# arcade2.net
KiCad netlist of a schematic drawn in EAGLE
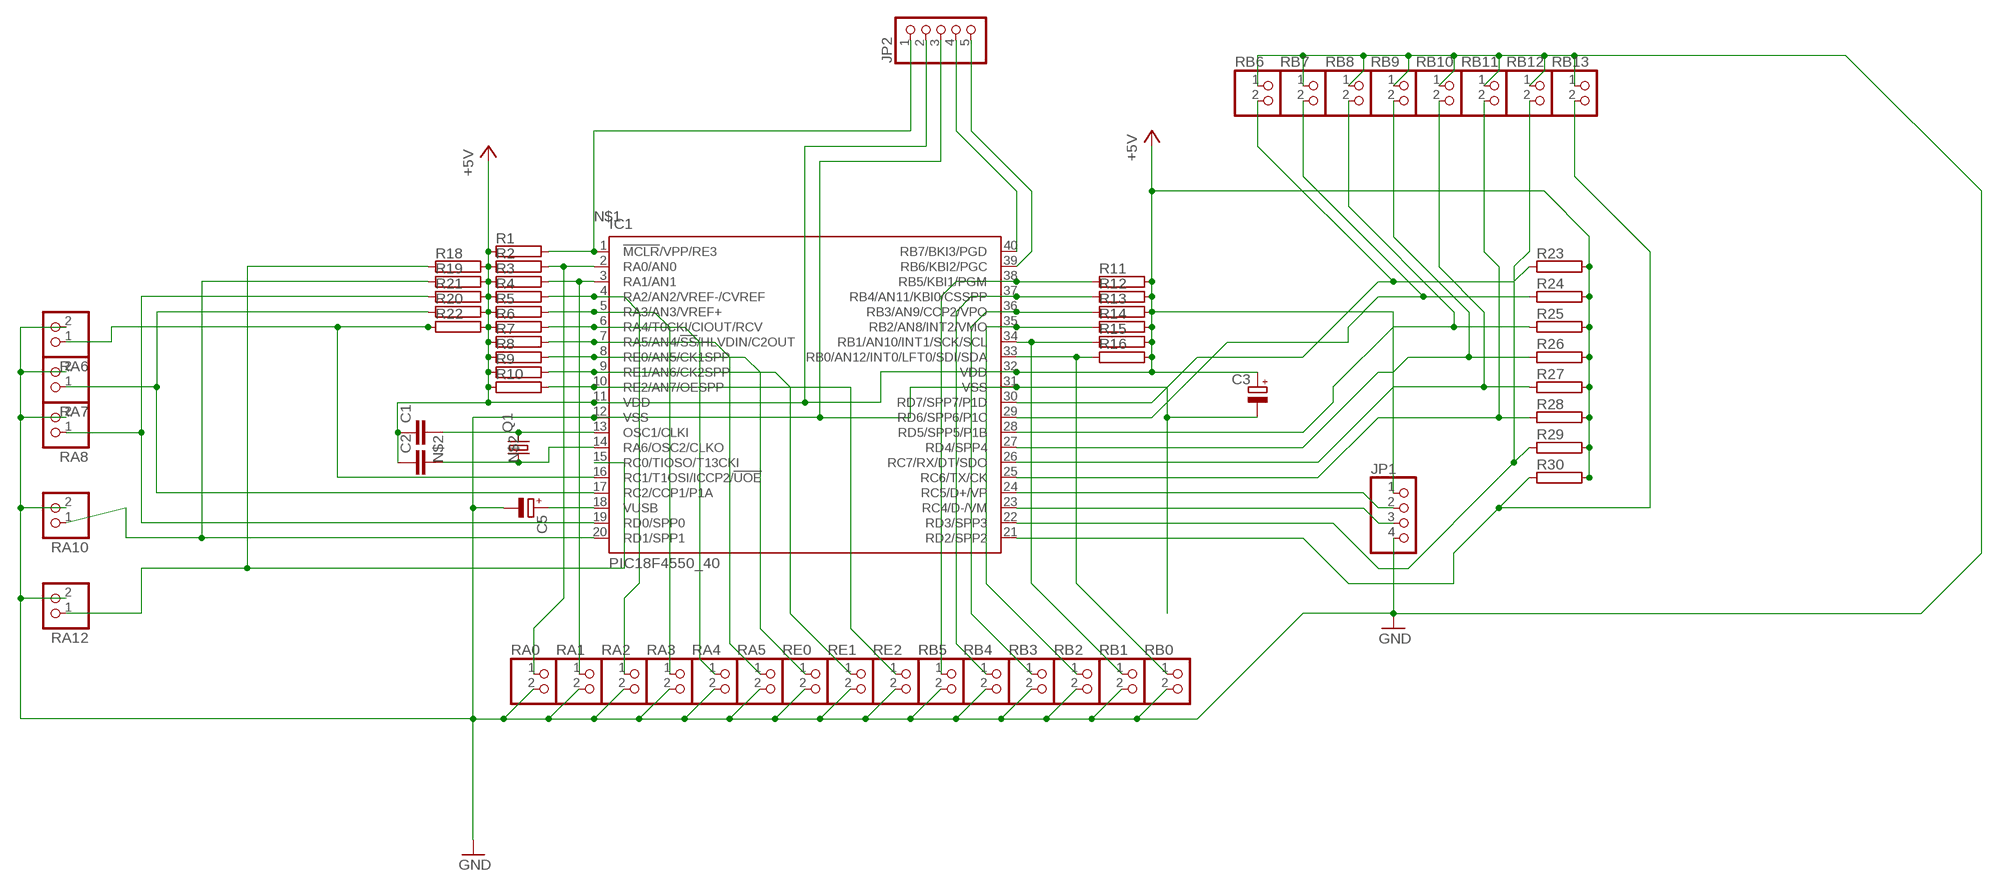
[diagram p0: schematic, sheet 1]

(export (version "E")
  (design (tool "Eeschema 10.0.6"))
  (components
    (comp (ref "C1")
      (value "C10/4")
      (footprint "eagle-import:C10B4")
      (libsource (lib "eagle-import") (part "C10/4"))
    )
    (comp (ref "C2")
      (value "C10/4")
      (footprint "eagle-import:C10B4")
      (libsource (lib "eagle-import") (part "C10/4"))
    )
    (comp (ref "C3")
      (value "CPOL-EUB45181C")
      (footprint "eagle-import:B45181C")
      (libsource (lib "eagle-import") (part "CPOL-EUB45181C"))
    )
    (comp (ref "C5")
      (value "CPOL-EUB45181C")
      (footprint "eagle-import:B45181C")
      (libsource (lib "eagle-import") (part "CPOL-EUB45181C"))
    )
    (comp (ref "IC1")
      (value "PIC18F4550_40")
      (footprint "eagle-import:DIL40")
      (fields (field (name "MF") "MICROCHIP") (field (name "MPN") "PIC18F4550-I/P"))
      (libsource (lib "eagle-import") (part "PIC18F4_40550"))
    )
    (comp (ref "JP1")
      (value "PINHD-1X4/90")
      (footprint "eagle-import:1X04_90")
      (libsource (lib "eagle-import") (part "PINHD-1X4/90"))
    )
    (comp (ref "JP2")
      (value "PINHD-1X5/90")
      (footprint "eagle-import:1X05_90")
      (libsource (lib "eagle-import") (part "PINHD-1X5/90"))
    )
    (comp (ref "Q1")
      (value "CRYSTALHC33U-V")
      (footprint "eagle-import:HC33U-V")
      (libsource (lib "eagle-import") (part "CRYSTALHC33U-V"))
    )
    (comp (ref "R1")
      (value "RAC01")
      (footprint "eagle-import:AC01")
      (libsource (lib "eagle-import") (part "RAC01"))
    )
    (comp (ref "R2")
      (value "RAC01")
      (footprint "eagle-import:AC01")
      (libsource (lib "eagle-import") (part "RAC01"))
    )
    (comp (ref "R3")
      (value "RAC01")
      (footprint "eagle-import:AC01")
      (libsource (lib "eagle-import") (part "RAC01"))
    )
    (comp (ref "R4")
      (value "RAC01")
      (footprint "eagle-import:AC01")
      (libsource (lib "eagle-import") (part "RAC01"))
    )
    (comp (ref "R5")
      (value "RAC01")
      (footprint "eagle-import:AC01")
      (libsource (lib "eagle-import") (part "RAC01"))
    )
    (comp (ref "R6")
      (value "RAC01")
      (footprint "eagle-import:AC01")
      (libsource (lib "eagle-import") (part "RAC01"))
    )
    (comp (ref "R7")
      (value "RAC01")
      (footprint "eagle-import:AC01")
      (libsource (lib "eagle-import") (part "RAC01"))
    )
    (comp (ref "R8")
      (value "RAC01")
      (footprint "eagle-import:AC01")
      (libsource (lib "eagle-import") (part "RAC01"))
    )
    (comp (ref "R9")
      (value "RAC01")
      (footprint "eagle-import:AC01")
      (libsource (lib "eagle-import") (part "RAC01"))
    )
    (comp (ref "R10")
      (value "RAC01")
      (footprint "eagle-import:AC01")
      (libsource (lib "eagle-import") (part "RAC01"))
    )
    (comp (ref "R11")
      (value "RAC01")
      (footprint "eagle-import:AC01")
      (libsource (lib "eagle-import") (part "RAC01"))
    )
    (comp (ref "R12")
      (value "RAC01")
      (footprint "eagle-import:AC01")
      (libsource (lib "eagle-import") (part "RAC01"))
    )
    (comp (ref "R13")
      (value "RAC01")
      (footprint "eagle-import:AC01")
      (libsource (lib "eagle-import") (part "RAC01"))
    )
    (comp (ref "R14")
      (value "RAC01")
      (footprint "eagle-import:AC01")
      (libsource (lib "eagle-import") (part "RAC01"))
    )
    (comp (ref "R15")
      (value "RAC01")
      (footprint "eagle-import:AC01")
      (libsource (lib "eagle-import") (part "RAC01"))
    )
    (comp (ref "R16")
      (value "RAC01")
      (footprint "eagle-import:AC01")
      (libsource (lib "eagle-import") (part "RAC01"))
    )
    (comp (ref "R18")
      (value "RAC01")
      (footprint "eagle-import:AC01")
      (libsource (lib "eagle-import") (part "RAC01"))
    )
    (comp (ref "R19")
      (value "RAC01")
      (footprint "eagle-import:AC01")
      (libsource (lib "eagle-import") (part "RAC01"))
    )
    (comp (ref "R20")
      (value "RAC01")
      (footprint "eagle-import:AC01")
      (libsource (lib "eagle-import") (part "RAC01"))
    )
    (comp (ref "R21")
      (value "RAC01")
      (footprint "eagle-import:AC01")
      (libsource (lib "eagle-import") (part "RAC01"))
    )
    (comp (ref "R22")
      (value "RAC01")
      (footprint "eagle-import:AC01")
      (libsource (lib "eagle-import") (part "RAC01"))
    )
    (comp (ref "R23")
      (value "RAC01")
      (footprint "eagle-import:AC01")
      (libsource (lib "eagle-import") (part "RAC01"))
    )
    (comp (ref "R24")
      (value "RAC01")
      (footprint "eagle-import:AC01")
      (libsource (lib "eagle-import") (part "RAC01"))
    )
    (comp (ref "R25")
      (value "RAC01")
      (footprint "eagle-import:AC01")
      (libsource (lib "eagle-import") (part "RAC01"))
    )
    (comp (ref "R26")
      (value "RAC01")
      (footprint "eagle-import:AC01")
      (libsource (lib "eagle-import") (part "RAC01"))
    )
    (comp (ref "R27")
      (value "RAC01")
      (footprint "eagle-import:AC01")
      (libsource (lib "eagle-import") (part "RAC01"))
    )
    (comp (ref "R28")
      (value "RAC01")
      (footprint "eagle-import:AC01")
      (libsource (lib "eagle-import") (part "RAC01"))
    )
    (comp (ref "R29")
      (value "RAC01")
      (footprint "eagle-import:AC01")
      (libsource (lib "eagle-import") (part "RAC01"))
    )
    (comp (ref "R30")
      (value "RAC01")
      (footprint "eagle-import:AC01")
      (libsource (lib "eagle-import") (part "RAC01"))
    )
    (comp (ref "RA0")
      (value "PINHD-1X2/90")
      (footprint "eagle-import:1X02_90")
      (libsource (lib "eagle-import") (part "PINHD-1X2/90"))
    )
    (comp (ref "RA1")
      (value "PINHD-1X2/90")
      (footprint "eagle-import:1X02_90")
      (libsource (lib "eagle-import") (part "PINHD-1X2/90"))
    )
    (comp (ref "RA2")
      (value "PINHD-1X2/90")
      (footprint "eagle-import:1X02_90")
      (libsource (lib "eagle-import") (part "PINHD-1X2/90"))
    )
    (comp (ref "RA3")
      (value "PINHD-1X2/90")
      (footprint "eagle-import:1X02_90")
      (libsource (lib "eagle-import") (part "PINHD-1X2/90"))
    )
    (comp (ref "RA4")
      (value "PINHD-1X2/90")
      (footprint "eagle-import:1X02_90")
      (libsource (lib "eagle-import") (part "PINHD-1X2/90"))
    )
    (comp (ref "RA5")
      (value "PINHD-1X2/90")
      (footprint "eagle-import:1X02_90")
      (libsource (lib "eagle-import") (part "PINHD-1X2/90"))
    )
    (comp (ref "RA6")
      (value "PINHD-1X2/90")
      (footprint "eagle-import:1X02_90")
      (libsource (lib "eagle-import") (part "PINHD-1X2/90"))
    )
    (comp (ref "RA7")
      (value "PINHD-1X2/90")
      (footprint "eagle-import:1X02_90")
      (libsource (lib "eagle-import") (part "PINHD-1X2/90"))
    )
    (comp (ref "RA8")
      (value "PINHD-1X2/90")
      (footprint "eagle-import:1X02_90")
      (libsource (lib "eagle-import") (part "PINHD-1X2/90"))
    )
    (comp (ref "RA10")
      (value "PINHD-1X2/90")
      (footprint "eagle-import:1X02_90")
      (libsource (lib "eagle-import") (part "PINHD-1X2/90"))
    )
    (comp (ref "RA12")
      (value "PINHD-1X2/90")
      (footprint "eagle-import:1X02_90")
      (libsource (lib "eagle-import") (part "PINHD-1X2/90"))
    )
    (comp (ref "RB0")
      (value "PINHD-1X2/90")
      (footprint "eagle-import:1X02_90")
      (libsource (lib "eagle-import") (part "PINHD-1X2/90"))
    )
    (comp (ref "RB1")
      (value "PINHD-1X2/90")
      (footprint "eagle-import:1X02_90")
      (libsource (lib "eagle-import") (part "PINHD-1X2/90"))
    )
    (comp (ref "RB2")
      (value "PINHD-1X2/90")
      (footprint "eagle-import:1X02_90")
      (libsource (lib "eagle-import") (part "PINHD-1X2/90"))
    )
    (comp (ref "RB3")
      (value "PINHD-1X2/90")
      (footprint "eagle-import:1X02_90")
      (libsource (lib "eagle-import") (part "PINHD-1X2/90"))
    )
    (comp (ref "RB4")
      (value "PINHD-1X2/90")
      (footprint "eagle-import:1X02_90")
      (libsource (lib "eagle-import") (part "PINHD-1X2/90"))
    )
    (comp (ref "RB5")
      (value "PINHD-1X2/90")
      (footprint "eagle-import:1X02_90")
      (libsource (lib "eagle-import") (part "PINHD-1X2/90"))
    )
    (comp (ref "RB6")
      (value "PINHD-1X2/90")
      (footprint "eagle-import:1X02_90")
      (libsource (lib "eagle-import") (part "PINHD-1X2/90"))
    )
    (comp (ref "RB7")
      (value "PINHD-1X2/90")
      (footprint "eagle-import:1X02_90")
      (libsource (lib "eagle-import") (part "PINHD-1X2/90"))
    )
    (comp (ref "RB8")
      (value "PINHD-1X2/90")
      (footprint "eagle-import:1X02_90")
      (libsource (lib "eagle-import") (part "PINHD-1X2/90"))
    )
    (comp (ref "RB9")
      (value "PINHD-1X2/90")
      (footprint "eagle-import:1X02_90")
      (libsource (lib "eagle-import") (part "PINHD-1X2/90"))
    )
    (comp (ref "RB10")
      (value "PINHD-1X2/90")
      (footprint "eagle-import:1X02_90")
      (libsource (lib "eagle-import") (part "PINHD-1X2/90"))
    )
    (comp (ref "RB11")
      (value "PINHD-1X2/90")
      (footprint "eagle-import:1X02_90")
      (libsource (lib "eagle-import") (part "PINHD-1X2/90"))
    )
    (comp (ref "RB12")
      (value "PINHD-1X2/90")
      (footprint "eagle-import:1X02_90")
      (libsource (lib "eagle-import") (part "PINHD-1X2/90"))
    )
    (comp (ref "RB13")
      (value "PINHD-1X2/90")
      (footprint "eagle-import:1X02_90")
      (libsource (lib "eagle-import") (part "PINHD-1X2/90"))
    )
    (comp (ref "RE0")
      (value "PINHD-1X2/90")
      (footprint "eagle-import:1X02_90")
      (libsource (lib "eagle-import") (part "PINHD-1X2/90"))
    )
    (comp (ref "RE1")
      (value "PINHD-1X2/90")
      (footprint "eagle-import:1X02_90")
      (libsource (lib "eagle-import") (part "PINHD-1X2/90"))
    )
    (comp (ref "RE2")
      (value "PINHD-1X2/90")
      (footprint "eagle-import:1X02_90")
      (libsource (lib "eagle-import") (part "PINHD-1X2/90"))
    )
  )
  (nets
    (net (code "1") (name "+5V") (class "Default")
      (node (ref "C1") (pin "1") (pinfunction "1_1") (pintype "passive"))
      (node (ref "C2") (pin "1") (pinfunction "1_1") (pintype "passive"))
      (node (ref "C3") (pin "+") (pinfunction "+_+") (pintype "passive"))
      (node (ref "IC1") (pin "11") (pinfunction "VDD_11") (pintype "power_in"))
      (node (ref "IC1") (pin "32") (pinfunction "VDD_32") (pintype "power_in"))
      (node (ref "JP1") (pin "1") (pinfunction "1_1") (pintype "passive"))
      (node (ref "JP2") (pin "2") (pinfunction "2_2") (pintype "passive"))
      (node (ref "R1") (pin "1") (pinfunction "1_1") (pintype "passive"))
      (node (ref "R10") (pin "1") (pinfunction "1_1") (pintype "passive"))
      (node (ref "R11") (pin "2") (pinfunction "2_2") (pintype "passive"))
      (node (ref "R12") (pin "2") (pinfunction "2_2") (pintype "passive"))
      (node (ref "R13") (pin "2") (pinfunction "2_2") (pintype "passive"))
      (node (ref "R14") (pin "2") (pinfunction "2_2") (pintype "passive"))
      (node (ref "R15") (pin "2") (pinfunction "2_2") (pintype "passive"))
      (node (ref "R16") (pin "2") (pinfunction "2_2") (pintype "passive"))
      (node (ref "R18") (pin "2") (pinfunction "2_2") (pintype "passive"))
      (node (ref "R19") (pin "2") (pinfunction "2_2") (pintype "passive"))
      (node (ref "R2") (pin "1") (pinfunction "1_1") (pintype "passive"))
      (node (ref "R20") (pin "2") (pinfunction "2_2") (pintype "passive"))
      (node (ref "R21") (pin "2") (pinfunction "2_2") (pintype "passive"))
      (node (ref "R22") (pin "2") (pinfunction "2_2") (pintype "passive"))
      (node (ref "R23") (pin "2") (pinfunction "2_2") (pintype "passive"))
      (node (ref "R24") (pin "2") (pinfunction "2_2") (pintype "passive"))
      (node (ref "R25") (pin "2") (pinfunction "2_2") (pintype "passive"))
      (node (ref "R26") (pin "2") (pinfunction "2_2") (pintype "passive"))
      (node (ref "R27") (pin "2") (pinfunction "2_2") (pintype "passive"))
      (node (ref "R28") (pin "2") (pinfunction "2_2") (pintype "passive"))
      (node (ref "R29") (pin "2") (pinfunction "2_2") (pintype "passive"))
      (node (ref "R3") (pin "1") (pinfunction "1_1") (pintype "passive"))
      (node (ref "R30") (pin "2") (pinfunction "2_2") (pintype "passive"))
      (node (ref "R4") (pin "1") (pinfunction "1_1") (pintype "passive"))
      (node (ref "R5") (pin "1") (pinfunction "1_1") (pintype "passive"))
      (node (ref "R6") (pin "1") (pinfunction "1_1") (pintype "passive"))
      (node (ref "R7") (pin "1") (pinfunction "1_1") (pintype "passive"))
      (node (ref "R8") (pin "1") (pinfunction "1_1") (pintype "passive"))
      (node (ref "R9") (pin "1") (pinfunction "1_1") (pintype "passive"))
    )
    (net (code "2") (name "/N$1") (class "Default")
      (node (ref "IC1") (pin "1") (pinfunction "~{MCLR}/VPP/RE3_1") (pintype "input"))
      (node (ref "JP2") (pin "1") (pinfunction "1_1") (pintype "passive"))
      (node (ref "R1") (pin "2") (pinfunction "2_2") (pintype "passive"))
    )
    (net (code "3") (name "/N$2") (class "Default")
      (node (ref "C2") (pin "2") (pinfunction "2_2") (pintype "passive"))
      (node (ref "IC1") (pin "14") (pinfunction "RA6/OSC2/CLKO_14") (pintype "output"))
      (node (ref "Q1") (pin "1") (pinfunction "1_1") (pintype "passive"))
    )
    (net (code "4") (name "GND") (class "Default")
      (node (ref "C3") (pin "-") (pinfunction "-_-") (pintype "passive"))
      (node (ref "C5") (pin "-") (pinfunction "-_-") (pintype "passive"))
      (node (ref "IC1") (pin "12") (pinfunction "VSS_12") (pintype "power_in"))
      (node (ref "IC1") (pin "31") (pinfunction "VSS_31") (pintype "power_in"))
      (node (ref "JP1") (pin "4") (pinfunction "4_4") (pintype "passive"))
      (node (ref "JP2") (pin "3") (pinfunction "3_3") (pintype "passive"))
      (node (ref "RA0") (pin "2") (pinfunction "2_2") (pintype "passive"))
      (node (ref "RA1") (pin "2") (pinfunction "2_2") (pintype "passive"))
      (node (ref "RA10") (pin "2") (pinfunction "2_2") (pintype "passive"))
      (node (ref "RA12") (pin "2") (pinfunction "2_2") (pintype "passive"))
      (node (ref "RA2") (pin "2") (pinfunction "2_2") (pintype "passive"))
      (node (ref "RA3") (pin "2") (pinfunction "2_2") (pintype "passive"))
      (node (ref "RA4") (pin "2") (pinfunction "2_2") (pintype "passive"))
      (node (ref "RA5") (pin "2") (pinfunction "2_2") (pintype "passive"))
      (node (ref "RA6") (pin "2") (pinfunction "2_2") (pintype "passive"))
      (node (ref "RA7") (pin "2") (pinfunction "2_2") (pintype "passive"))
      (node (ref "RA8") (pin "2") (pinfunction "2_2") (pintype "passive"))
      (node (ref "RB0") (pin "2") (pinfunction "2_2") (pintype "passive"))
      (node (ref "RB1") (pin "2") (pinfunction "2_2") (pintype "passive"))
      (node (ref "RB10") (pin "1") (pinfunction "1_1") (pintype "passive"))
      (node (ref "RB11") (pin "1") (pinfunction "1_1") (pintype "passive"))
      (node (ref "RB12") (pin "1") (pinfunction "1_1") (pintype "passive"))
      (node (ref "RB13") (pin "1") (pinfunction "1_1") (pintype "passive"))
      (node (ref "RB2") (pin "2") (pinfunction "2_2") (pintype "passive"))
      (node (ref "RB3") (pin "2") (pinfunction "2_2") (pintype "passive"))
      (node (ref "RB4") (pin "2") (pinfunction "2_2") (pintype "passive"))
      (node (ref "RB5") (pin "2") (pinfunction "2_2") (pintype "passive"))
      (node (ref "RB6") (pin "1") (pinfunction "1_1") (pintype "passive"))
      (node (ref "RB7") (pin "1") (pinfunction "1_1") (pintype "passive"))
      (node (ref "RB8") (pin "1") (pinfunction "1_1") (pintype "passive"))
      (node (ref "RB9") (pin "1") (pinfunction "1_1") (pintype "passive"))
      (node (ref "RE0") (pin "2") (pinfunction "2_2") (pintype "passive"))
      (node (ref "RE1") (pin "2") (pinfunction "2_2") (pintype "passive"))
      (node (ref "RE2") (pin "2") (pinfunction "2_2") (pintype "passive"))
    )
    (net (code "5") (name "Net-(IC1-OSC1{slash}CLKI)") (class "Default")
      (node (ref "C1") (pin "2") (pinfunction "2_2") (pintype "passive"))
      (node (ref "IC1") (pin "13") (pinfunction "OSC1/CLKI_13") (pintype "input"))
      (node (ref "Q1") (pin "2") (pinfunction "2_2") (pintype "passive"))
    )
    (net (code "6") (name "Net-(IC1-RA0{slash}AN0)") (class "Default")
      (node (ref "IC1") (pin "2") (pinfunction "RA0/AN0_2") (pintype "bidirectional"))
      (node (ref "R2") (pin "2") (pinfunction "2_2") (pintype "passive"))
      (node (ref "RA0") (pin "1") (pinfunction "1_1") (pintype "passive"))
    )
    (net (code "7") (name "Net-(IC1-RA1{slash}AN1)") (class "Default")
      (node (ref "IC1") (pin "3") (pinfunction "RA1/AN1_3") (pintype "bidirectional"))
      (node (ref "R3") (pin "2") (pinfunction "2_2") (pintype "passive"))
      (node (ref "RA1") (pin "1") (pinfunction "1_1") (pintype "passive"))
    )
    (net (code "8") (name "Net-(IC1-RA2{slash}AN2{slash}VREF-{slash}CVREF)") (class "Default")
      (node (ref "IC1") (pin "4") (pinfunction "RA2/AN2/VREF-/CVREF_4") (pintype "bidirectional"))
      (node (ref "R4") (pin "2") (pinfunction "2_2") (pintype "passive"))
      (node (ref "RA2") (pin "1") (pinfunction "1_1") (pintype "passive"))
    )
    (net (code "9") (name "Net-(IC1-RA3{slash}AN3{slash}VREF+)") (class "Default")
      (node (ref "IC1") (pin "5") (pinfunction "RA3/AN3/VREF+_5") (pintype "bidirectional"))
      (node (ref "R5") (pin "2") (pinfunction "2_2") (pintype "passive"))
      (node (ref "RA3") (pin "1") (pinfunction "1_1") (pintype "passive"))
    )
    (net (code "10") (name "Net-(IC1-RA4{slash}T0CKI{slash}CIOUT{slash}RCV)") (class "Default")
      (node (ref "IC1") (pin "6") (pinfunction "RA4/T0CKI/CIOUT/RCV_6") (pintype "bidirectional"))
      (node (ref "R6") (pin "2") (pinfunction "2_2") (pintype "passive"))
      (node (ref "RA4") (pin "1") (pinfunction "1_1") (pintype "passive"))
    )
    (net (code "11") (name "Net-(IC1-RA5{slash}AN4{slash}~{SS}{slash}HLVDIN{slash}C2OUT)") (class "Default")
      (node (ref "IC1") (pin "7") (pinfunction "RA5/AN4/~{SS}/HLVDIN/C2OUT_7") (pintype "bidirectional"))
      (node (ref "R7") (pin "2") (pinfunction "2_2") (pintype "passive"))
      (node (ref "RA5") (pin "1") (pinfunction "1_1") (pintype "passive"))
    )
    (net (code "12") (name "Net-(IC1-RB0{slash}AN12{slash}INT0{slash}LFT0{slash}SDI{slash}SDA)") (class "Default")
      (node (ref "IC1") (pin "33") (pinfunction "RB0/AN12/INT0/LFT0/SDI/SDA_33") (pintype "bidirectional"))
      (node (ref "R16") (pin "1") (pinfunction "1_1") (pintype "passive"))
      (node (ref "RB0") (pin "1") (pinfunction "1_1") (pintype "passive"))
    )
    (net (code "13") (name "Net-(IC1-RB1{slash}AN10{slash}INT1{slash}SCK{slash}SCL)") (class "Default")
      (node (ref "IC1") (pin "34") (pinfunction "RB1/AN10/INT1/SCK/SCL_34") (pintype "bidirectional"))
      (node (ref "R15") (pin "1") (pinfunction "1_1") (pintype "passive"))
      (node (ref "RB1") (pin "1") (pinfunction "1_1") (pintype "passive"))
    )
    (net (code "14") (name "Net-(IC1-RB2{slash}AN8{slash}INT2{slash}VMO)") (class "Default")
      (node (ref "IC1") (pin "35") (pinfunction "RB2/AN8/INT2/VMO_35") (pintype "bidirectional"))
      (node (ref "R14") (pin "1") (pinfunction "1_1") (pintype "passive"))
      (node (ref "RB2") (pin "1") (pinfunction "1_1") (pintype "passive"))
    )
    (net (code "15") (name "Net-(IC1-RB3{slash}AN9{slash}CCP2{slash}VPO)") (class "Default")
      (node (ref "IC1") (pin "36") (pinfunction "RB3/AN9/CCP2/VPO_36") (pintype "bidirectional"))
      (node (ref "R13") (pin "1") (pinfunction "1_1") (pintype "passive"))
      (node (ref "RB3") (pin "1") (pinfunction "1_1") (pintype "passive"))
    )
    (net (code "16") (name "Net-(IC1-RB4{slash}AN11{slash}KBI0{slash}CSSPP)") (class "Default")
      (node (ref "IC1") (pin "37") (pinfunction "RB4/AN11/KBI0/CSSPP_37") (pintype "bidirectional"))
      (node (ref "R12") (pin "1") (pinfunction "1_1") (pintype "passive"))
      (node (ref "RB4") (pin "1") (pinfunction "1_1") (pintype "passive"))
    )
    (net (code "17") (name "Net-(IC1-RB5{slash}KBI1{slash}PGM)") (class "Default")
      (node (ref "IC1") (pin "38") (pinfunction "RB5/KBI1/PGM_38") (pintype "bidirectional"))
      (node (ref "R11") (pin "1") (pinfunction "1_1") (pintype "passive"))
      (node (ref "RB5") (pin "1") (pinfunction "1_1") (pintype "passive"))
    )
    (net (code "18") (name "Net-(IC1-RB6{slash}KBI2{slash}PGC)") (class "Default")
      (node (ref "IC1") (pin "39") (pinfunction "RB6/KBI2/PGC_39") (pintype "bidirectional"))
      (node (ref "JP2") (pin "5") (pinfunction "5_5") (pintype "passive"))
    )
    (net (code "19") (name "Net-(IC1-RB7{slash}BKI3{slash}PGD)") (class "Default")
      (node (ref "IC1") (pin "40") (pinfunction "RB7/BKI3/PGD_40") (pintype "bidirectional"))
      (node (ref "JP2") (pin "4") (pinfunction "4_4") (pintype "passive"))
    )
    (net (code "20") (name "Net-(IC1-RC0{slash}TIOSO{slash}T13CKI)") (class "Default")
      (node (ref "IC1") (pin "15") (pinfunction "RC0/TIOSO/T13CKI_15") (pintype "bidirectional"))
      (node (ref "R18") (pin "1") (pinfunction "1_1") (pintype "passive"))
      (node (ref "RA12") (pin "1") (pinfunction "1_1") (pintype "passive"))
    )
    (net (code "21") (name "Net-(IC1-RC1{slash}T1OSI{slash}ICCP2{slash}~{UOE})") (class "Default")
      (node (ref "IC1") (pin "16") (pinfunction "RC1/T1OSI/ICCP2/~{UOE}_16") (pintype "bidirectional"))
      (node (ref "R22") (pin "1") (pinfunction "1_1") (pintype "passive"))
      (node (ref "RA6") (pin "1") (pinfunction "1_1") (pintype "passive"))
    )
    (net (code "22") (name "Net-(IC1-RC2{slash}CCP1{slash}P1A)") (class "Default")
      (node (ref "IC1") (pin "17") (pinfunction "RC2/CCP1/P1A_17") (pintype "bidirectional"))
      (node (ref "R20") (pin "1") (pinfunction "1_1") (pintype "passive"))
      (node (ref "RA7") (pin "1") (pinfunction "1_1") (pintype "passive"))
    )
    (net (code "23") (name "Net-(IC1-RC4{slash}D-{slash}VM)") (class "Default")
      (node (ref "IC1") (pin "23") (pinfunction "RC4/D-/VM_23") (pintype "bidirectional"))
      (node (ref "JP1") (pin "3") (pinfunction "3_3") (pintype "passive"))
    )
    (net (code "24") (name "Net-(IC1-RC5{slash}D+{slash}VP)") (class "Default")
      (node (ref "IC1") (pin "24") (pinfunction "RC5/D+/VP_24") (pintype "bidirectional"))
      (node (ref "JP1") (pin "2") (pinfunction "2_2") (pintype "passive"))
    )
    (net (code "25") (name "Net-(IC1-RC6{slash}TX{slash}CK)") (class "Default")
      (node (ref "IC1") (pin "25") (pinfunction "RC6/TX/CK_25") (pintype "bidirectional"))
      (node (ref "R28") (pin "1") (pinfunction "1_1") (pintype "passive"))
      (node (ref "RB11") (pin "2") (pinfunction "2_2") (pintype "passive"))
    )
    (net (code "26") (name "Net-(IC1-RC7{slash}RX{slash}DT{slash}SDO)") (class "Default")
      (node (ref "IC1") (pin "26") (pinfunction "RC7/RX/DT/SDO_26") (pintype "bidirectional"))
      (node (ref "R27") (pin "1") (pinfunction "1_1") (pintype "passive"))
      (node (ref "RB10") (pin "2") (pinfunction "2_2") (pintype "passive"))
    )
    (net (code "27") (name "Net-(IC1-RD0{slash}SPP0)") (class "Default")
      (node (ref "IC1") (pin "19") (pinfunction "RD0/SPP0_19") (pintype "bidirectional"))
      (node (ref "R21") (pin "1") (pinfunction "1_1") (pintype "passive"))
      (node (ref "RA8") (pin "1") (pinfunction "1_1") (pintype "passive"))
    )
    (net (code "28") (name "Net-(IC1-RD1{slash}SPP1)") (class "Default")
      (node (ref "IC1") (pin "20") (pinfunction "RD1/SPP1_20") (pintype "bidirectional"))
      (node (ref "R19") (pin "1") (pinfunction "1_1") (pintype "passive"))
      (node (ref "RA10") (pin "1") (pinfunction "1_1") (pintype "passive"))
    )
    (net (code "29") (name "Net-(IC1-RD2{slash}SPP2)") (class "Default")
      (node (ref "IC1") (pin "21") (pinfunction "RD2/SPP2_21") (pintype "bidirectional"))
      (node (ref "R30") (pin "1") (pinfunction "1_1") (pintype "passive"))
      (node (ref "RB13") (pin "2") (pinfunction "2_2") (pintype "passive"))
    )
    (net (code "30") (name "Net-(IC1-RD3{slash}SPP3)") (class "Default")
      (node (ref "IC1") (pin "22") (pinfunction "RD3/SPP3_22") (pintype "bidirectional"))
      (node (ref "R29") (pin "1") (pinfunction "1_1") (pintype "passive"))
      (node (ref "RB12") (pin "2") (pinfunction "2_2") (pintype "passive"))
    )
    (net (code "31") (name "Net-(IC1-RD4{slash}SPP4)") (class "Default")
      (node (ref "IC1") (pin "27") (pinfunction "RD4/SPP4_27") (pintype "bidirectional"))
      (node (ref "R26") (pin "1") (pinfunction "1_1") (pintype "passive"))
      (node (ref "RB9") (pin "2") (pinfunction "2_2") (pintype "passive"))
    )
    (net (code "32") (name "Net-(IC1-RD5{slash}SPP5{slash}P1B)") (class "Default")
      (node (ref "IC1") (pin "28") (pinfunction "RD5/SPP5/P1B_28") (pintype "bidirectional"))
      (node (ref "R25") (pin "1") (pinfunction "1_1") (pintype "passive"))
      (node (ref "RB8") (pin "2") (pinfunction "2_2") (pintype "passive"))
    )
    (net (code "33") (name "Net-(IC1-RD6{slash}SPP6{slash}P1C)") (class "Default")
      (node (ref "IC1") (pin "29") (pinfunction "RD6/SPP6/P1C_29") (pintype "bidirectional"))
      (node (ref "R24") (pin "1") (pinfunction "1_1") (pintype "passive"))
      (node (ref "RB7") (pin "2") (pinfunction "2_2") (pintype "passive"))
    )
    (net (code "34") (name "Net-(IC1-RD7{slash}SPP7{slash}P1D)") (class "Default")
      (node (ref "IC1") (pin "30") (pinfunction "RD7/SPP7/P1D_30") (pintype "bidirectional"))
      (node (ref "R23") (pin "1") (pinfunction "1_1") (pintype "passive"))
      (node (ref "RB6") (pin "2") (pinfunction "2_2") (pintype "passive"))
    )
    (net (code "35") (name "Net-(IC1-RE0{slash}AN5{slash}CK1SPP)") (class "Default")
      (node (ref "IC1") (pin "8") (pinfunction "RE0/AN5/CK1SPP_8") (pintype "bidirectional"))
      (node (ref "R8") (pin "2") (pinfunction "2_2") (pintype "passive"))
      (node (ref "RE0") (pin "1") (pinfunction "1_1") (pintype "passive"))
    )
    (net (code "36") (name "Net-(IC1-RE1{slash}AN6{slash}CK2SPP)") (class "Default")
      (node (ref "IC1") (pin "9") (pinfunction "RE1/AN6/CK2SPP_9") (pintype "bidirectional"))
      (node (ref "R9") (pin "2") (pinfunction "2_2") (pintype "passive"))
      (node (ref "RE1") (pin "1") (pinfunction "1_1") (pintype "passive"))
    )
    (net (code "37") (name "Net-(IC1-RE2{slash}AN7{slash}OESPP)") (class "Default")
      (node (ref "IC1") (pin "10") (pinfunction "RE2/AN7/OESPP_10") (pintype "bidirectional"))
      (node (ref "R10") (pin "2") (pinfunction "2_2") (pintype "passive"))
      (node (ref "RE2") (pin "1") (pinfunction "1_1") (pintype "passive"))
    )
    (net (code "38") (name "Net-(IC1-VUSB)") (class "Default")
      (node (ref "C5") (pin "+") (pinfunction "+_+") (pintype "passive"))
      (node (ref "IC1") (pin "18") (pinfunction "VUSB_18") (pintype "bidirectional"))
    )
  )
)
